# LED_circuits.net
KiCad netlist of a schematic drawn in Altium Designer
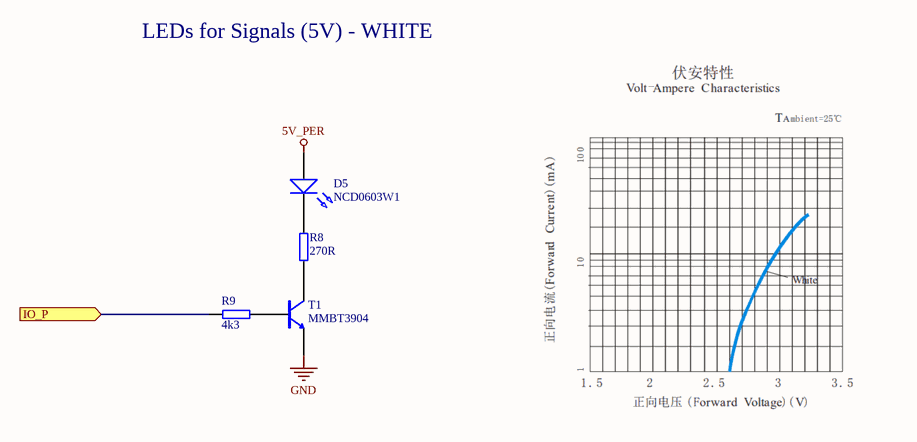
[diagram p0: LED_circuits.SchDoc]

(export (version "E")
  (design (tool "Eeschema 10.0.6"))
  (components
    (comp (ref "D5")
      (value "NCD0603W1")
      (footprint "WL-SMCW_0603")
      (description "White light 0603 Light Emitting Diodes (LED) ROHS")
      (fields
        (field (name "MANUFACTURER") "Foshan NationStar Optoelectronics")
        (field (name "LCSC PART NUMBER") "C84265")
        (field (name "CREATED FROM") "NDiringer")
      )
      (libsource (lib "user") (part "LED_WHITE"))
    )
    (comp (ref "R8")
      (value "270R")
      (footprint "RES 0603_1608")
      (fields
        (field (name "MANUFACTURER PART NUMBER") "0603WAF2700T5E")
        (field (name "MANUFACTURER") "UNI-ROYAL(Uniroyal Elec)")
        (field (name "TOLERANCE") "1%")
        (field (name "CREATED FROM") "NDiringer")
      )
      (libsource (lib "user") (part "Resistor"))
    )
    (comp (ref "R9")
      (value "4k3")
      (footprint "RES 0603_1608")
      (fields
        (field (name "MANUFACTURER PART NUMBER") "0603WAF4301T5E")
        (field (name "MANUFACTURER") "UNI-ROYAL(Uniroyal Elec)")
        (field (name "TOLERANCE") "1%")
        (field (name "CREATED FROM") "NDiringer")
      )
      (libsource (lib "user") (part "Resistor"))
    )
    (comp (ref "T1")
      (value "MMBT3904")
      (footprint "SOT95P280X145-3N")
      (fields
        (field (name "MANUFACTURER") "Jiangsu Changjing Electronics Technology Co., Ltd.")
        (field (name "LCSC PART NUMBER") "C20526")
        (field (name "CREATED FROM") "NDiringer")
      )
      (libsource (lib "user") (part "NPN-SOT23"))
    )
  )
  (nets
    (net (code "1") (name "/IO_P") (class "Default")
      (node (ref "R9") (pin "1") (pinfunction "1_1") (pintype "passive"))
    )
    (net (code "2") (name "5V_PER") (class "Default")
      (node (ref "D5") (pin "2") (pinfunction "A_2") (pintype "passive"))
    )
    (net (code "3") (name "GND") (class "Default")
      (node (ref "T1") (pin "2") (pinfunction "EMITTER_2") (pintype "passive"))
    )
    (net (code "4") (name "Net-(D5-K)") (class "Default")
      (node (ref "D5") (pin "1") (pinfunction "K_1") (pintype "passive"))
      (node (ref "R8") (pin "2") (pinfunction "2_2") (pintype "passive"))
    )
    (net (code "5") (name "Net-(T1-BASIS)") (class "Default")
      (node (ref "R9") (pin "2") (pinfunction "2_2") (pintype "passive"))
      (node (ref "T1") (pin "1") (pinfunction "BASIS_1") (pintype "passive"))
    )
    (net (code "6") (name "Net-(T1-COLLECTOR)") (class "Default")
      (node (ref "R8") (pin "1") (pinfunction "1_1") (pintype "passive"))
      (node (ref "T1") (pin "3") (pinfunction "COLLECTOR_3") (pintype "passive"))
    )
  )
)
